# Misc.net
KiCad netlist of a schematic drawn in Altium Designer
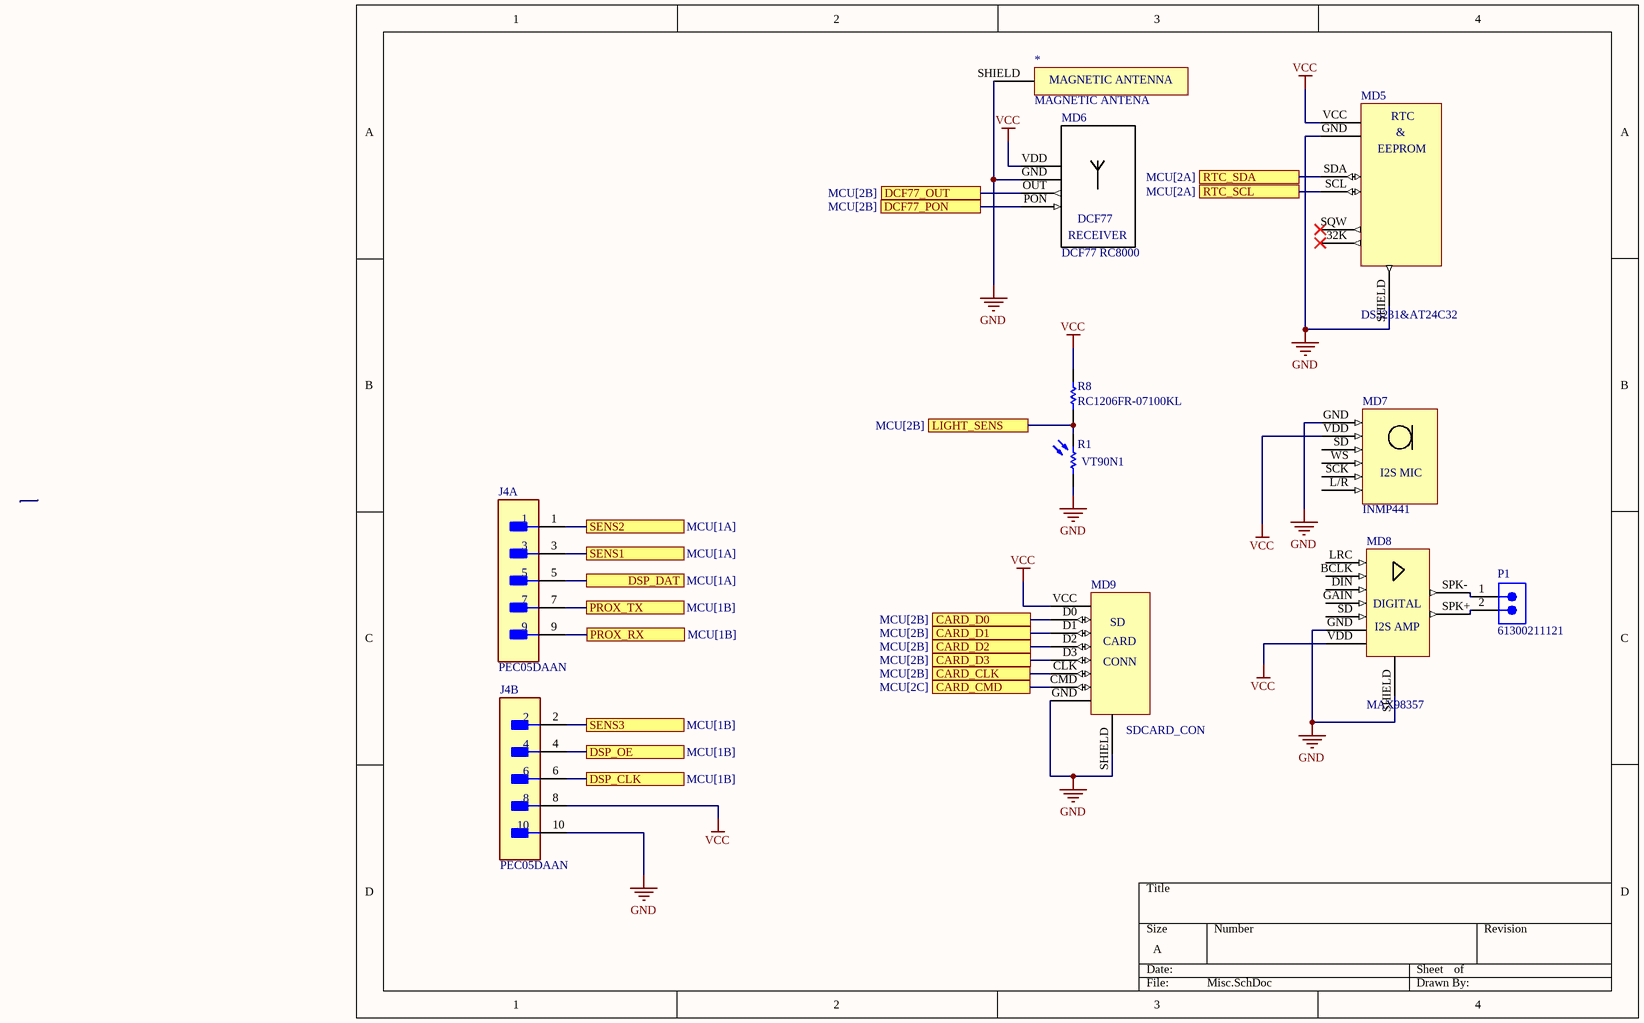
[diagram p0: Misc.SchDoc]

(export (version "E")
  (design (tool "Eeschema 10.0.6"))
  (components
    (comp (ref "*")
      (value "MAGNETIC ANTENA")
      (footprint "MAGNETIC ANTENA")
      (libsource (lib "NexieSpecific") (part "MAGNETIC ANTENA"))
    )
    (comp (ref "J4")
      (value "PEC05DAAN")
      (footprint "FP-PEC05DAAN-MFG")
      (description "CONN HEADER VERT 10POS 2.54MM")
      (libsource (lib "Altium Content Vault") (part "544f42128f4185dcb88ce1ce9bf1982"))
    )
    (comp (ref "MD5")
      (value "DS3231&AT24C32")
      (footprint "DS3231_MODULE")
      (libsource (lib "NexieSpecific") (part "RTC DS3231_MODULE"))
    )
    (comp (ref "MD6")
      (value "DCF77 RC8000")
      (footprint "DFC77_MODULE")
      (libsource (lib "NexieSpecific") (part "DCF77_MODULE"))
    )
    (comp (ref "MD7")
      (value "INMP441")
      (footprint "INMP441_i2s_microphone_module")
      (description "Digital microphone")
      (libsource (lib "NexieSpecific") (part "INMP441_I2S_MIC"))
    )
    (comp (ref "MD8")
      (value "MAX98357")
      (footprint "MAX98357")
      (libsource (lib "NexieSpecific") (part "MAX98357"))
    )
    (comp (ref "MD9")
      (value "SDCARD_CON")
      (footprint "SDCARD_CONN")
      (libsource (lib "NexieSpecific") (part "SDCARD_CON"))
    )
    (comp (ref "P1")
      (value "61300211121")
      (footprint "61300211121")
      (libsource (lib "Altium Content Vault") (part "Header_Male_1R_02P"))
    )
    (comp (ref "R1")
      (value "VT90N1")
      (footprint "EXCE-VT90N1")
      (description "Photoconductive Resistor, 200 kOhm, 100 V, 80 mW, -40 to 75 degC, 2-Pin THD, RoHS")
      (fields (field (name "MANUFACTURER") "Excelitas Technology"))
      (libsource (lib "Altium Content Vault") (part "PHOTO-RES-2"))
    )
    (comp (ref "R8")
      (value "RC1206FR-07100KL")
      (footprint "RESC3116X65X40ML10T20")
      (description "Chip Resistor, 100 KOhm, +/- 1%, 0.25 W, -55 to 155 degC, 1206 (3216 Metric), RoHS, Tape and Reel")
      (fields (field (name "TOLERANCE") "1%") (field (name "MANUFACTURER") "Yageo"))
      (libsource (lib "Altium Content Vault") (part "RES-2"))
    )
  )
  (nets
    (net (code "1") (name "/CARD_CLK") (class "Default")
      (node (ref "MD9") (pin "CLK") (pintype "bidirectional"))
    )
    (net (code "2") (name "/CARD_CMD") (class "Default")
      (node (ref "MD9") (pin "CMD") (pintype "bidirectional"))
    )
    (net (code "3") (name "/CARD_D0") (class "Default")
      (node (ref "MD9") (pin "D0") (pintype "bidirectional"))
    )
    (net (code "4") (name "/CARD_D1") (class "Default")
      (node (ref "MD9") (pin "D1") (pintype "bidirectional"))
    )
    (net (code "5") (name "/CARD_D2") (class "Default")
      (node (ref "MD9") (pin "D2") (pintype "bidirectional"))
    )
    (net (code "6") (name "/CARD_D3") (class "Default")
      (node (ref "MD9") (pin "D3") (pintype "bidirectional"))
    )
    (net (code "7") (name "/DCF77_OUT") (class "Default") (node (ref "MD6") (pin "OUT") (pintype "output")))
    (net (code "8") (name "/DCF77_PON") (class "Default") (node (ref "MD6") (pin "PON") (pintype "input")))
    (net (code "9") (name "/DSP_CLK") (class "Default")
      (node (ref "J4") (pin "6") (pinfunction "6_6") (pintype "passive"))
    )
    (net (code "10") (name "/DSP_DAT") (class "Default")
      (node (ref "J4") (pin "5") (pinfunction "5_5") (pintype "passive"))
    )
    (net (code "11") (name "/DSP_OE") (class "Default")
      (node (ref "J4") (pin "4") (pinfunction "4_4") (pintype "passive"))
    )
    (net (code "12") (name "/LIGHT_SENS") (class "Default")
      (node (ref "R1") (pin "2") (pinfunction "2_2") (pintype "passive"))
      (node (ref "R8") (pin "1") (pinfunction "1_1") (pintype "passive"))
    )
    (net (code "13") (name "/PROX_RX") (class "Default")
      (node (ref "J4") (pin "9") (pinfunction "9_9") (pintype "passive"))
    )
    (net (code "14") (name "/PROX_TX") (class "Default")
      (node (ref "J4") (pin "7") (pinfunction "7_7") (pintype "passive"))
    )
    (net (code "15") (name "/RTC_SCL") (class "Default")
      (node (ref "MD5") (pin "SCL") (pintype "bidirectional"))
    )
    (net (code "16") (name "/RTC_SDA") (class "Default")
      (node (ref "MD5") (pin "SDA") (pintype "bidirectional"))
    )
    (net (code "17") (name "/SENS1") (class "Default")
      (node (ref "J4") (pin "3") (pinfunction "3_3") (pintype "passive"))
    )
    (net (code "18") (name "/SENS2") (class "Default")
      (node (ref "J4") (pin "1") (pinfunction "1_1") (pintype "passive"))
    )
    (net (code "19") (name "/SENS3") (class "Default")
      (node (ref "J4") (pin "2") (pinfunction "2_2") (pintype "passive"))
    )
    (net (code "20") (name "GND") (class "Default")
      (node (ref "*") (pin "SHIELD") (pintype "passive"))
      (node (ref "J4") (pin "10") (pinfunction "10_10") (pintype "passive"))
      (node (ref "MD5") (pin "GND") (pintype "power_in"))
      (node (ref "MD5") (pin "SHIELD") (pintype "output"))
      (node (ref "MD6") (pin "GND") (pintype "power_in"))
      (node (ref "MD7") (pin "GND") (pintype "input"))
      (node (ref "MD8") (pin "GND") (pintype "power_in"))
      (node (ref "MD8") (pin "SHIELD") (pintype "power_in"))
      (node (ref "MD9") (pin "GND") (pintype "power_in"))
      (node (ref "MD9") (pin "SHIELD") (pintype "power_in"))
      (node (ref "R1") (pin "1") (pinfunction "1_1") (pintype "passive"))
    )
    (net (code "21") (name "Net-(MD8-PadSPK+)") (class "Default")
      (node (ref "MD8") (pin "SPK+") (pintype "output"))
      (node (ref "P1") (pin "2") (pinfunction "2_2") (pintype "passive"))
    )
    (net (code "22") (name "Net-(MD8-PadSPK-)") (class "Default")
      (node (ref "MD8") (pin "SPK-") (pintype "output"))
      (node (ref "P1") (pin "1") (pinfunction "1_1") (pintype "passive"))
    )
    (net (code "23") (name "VCC") (class "Default")
      (node (ref "J4") (pin "8") (pinfunction "8_8") (pintype "passive"))
      (node (ref "MD5") (pin "VCC") (pintype "power_in"))
      (node (ref "MD6") (pin "VDD") (pintype "power_in"))
      (node (ref "MD7") (pin "VDD") (pintype "input"))
      (node (ref "MD8") (pin "VDD") (pintype "power_in"))
      (node (ref "MD9") (pin "VCC") (pintype "power_in"))
      (node (ref "R8") (pin "2") (pinfunction "2_2") (pintype "passive"))
    )
    (net (code "24") (name "unconnected-(MD5-Pad32K)") (class "Default")
      (node (ref "MD5") (pin "32K") (pintype "output+no_connect"))
    )
    (net (code "25") (name "unconnected-(MD5-PadSQW)") (class "Default")
      (node (ref "MD5") (pin "SQW") (pintype "output+no_connect"))
    )
    (net (code "26") (name "unconnected-(MD7-PadL{slash}R)") (class "Default")
      (node (ref "MD7") (pin "L/R") (pintype "input"))
    )
    (net (code "27") (name "unconnected-(MD7-PadSCK)") (class "Default")
      (node (ref "MD7") (pin "SCK") (pintype "input"))
    )
    (net (code "28") (name "unconnected-(MD7-PadSD)") (class "Default")
      (node (ref "MD7") (pin "SD") (pintype "input"))
    )
    (net (code "29") (name "unconnected-(MD7-PadWS)") (class "Default")
      (node (ref "MD7") (pin "WS") (pintype "input"))
    )
    (net (code "30") (name "unconnected-(MD8-PadBCLK)") (class "Default")
      (node (ref "MD8") (pin "BCLK") (pintype "input"))
    )
    (net (code "31") (name "unconnected-(MD8-PadDIN)") (class "Default")
      (node (ref "MD8") (pin "DIN") (pintype "input"))
    )
    (net (code "32") (name "unconnected-(MD8-PadGAIN)") (class "Default")
      (node (ref "MD8") (pin "GAIN") (pintype "input"))
    )
    (net (code "33") (name "unconnected-(MD8-PadLRC)") (class "Default")
      (node (ref "MD8") (pin "LRC") (pintype "input"))
    )
    (net (code "34") (name "unconnected-(MD8-PadSD)") (class "Default")
      (node (ref "MD8") (pin "SD") (pintype "input"))
    )
  )
)
